# 4_cyber60-alps_periferals.net
KiCad netlist of a schematic drawn in Altium Designer
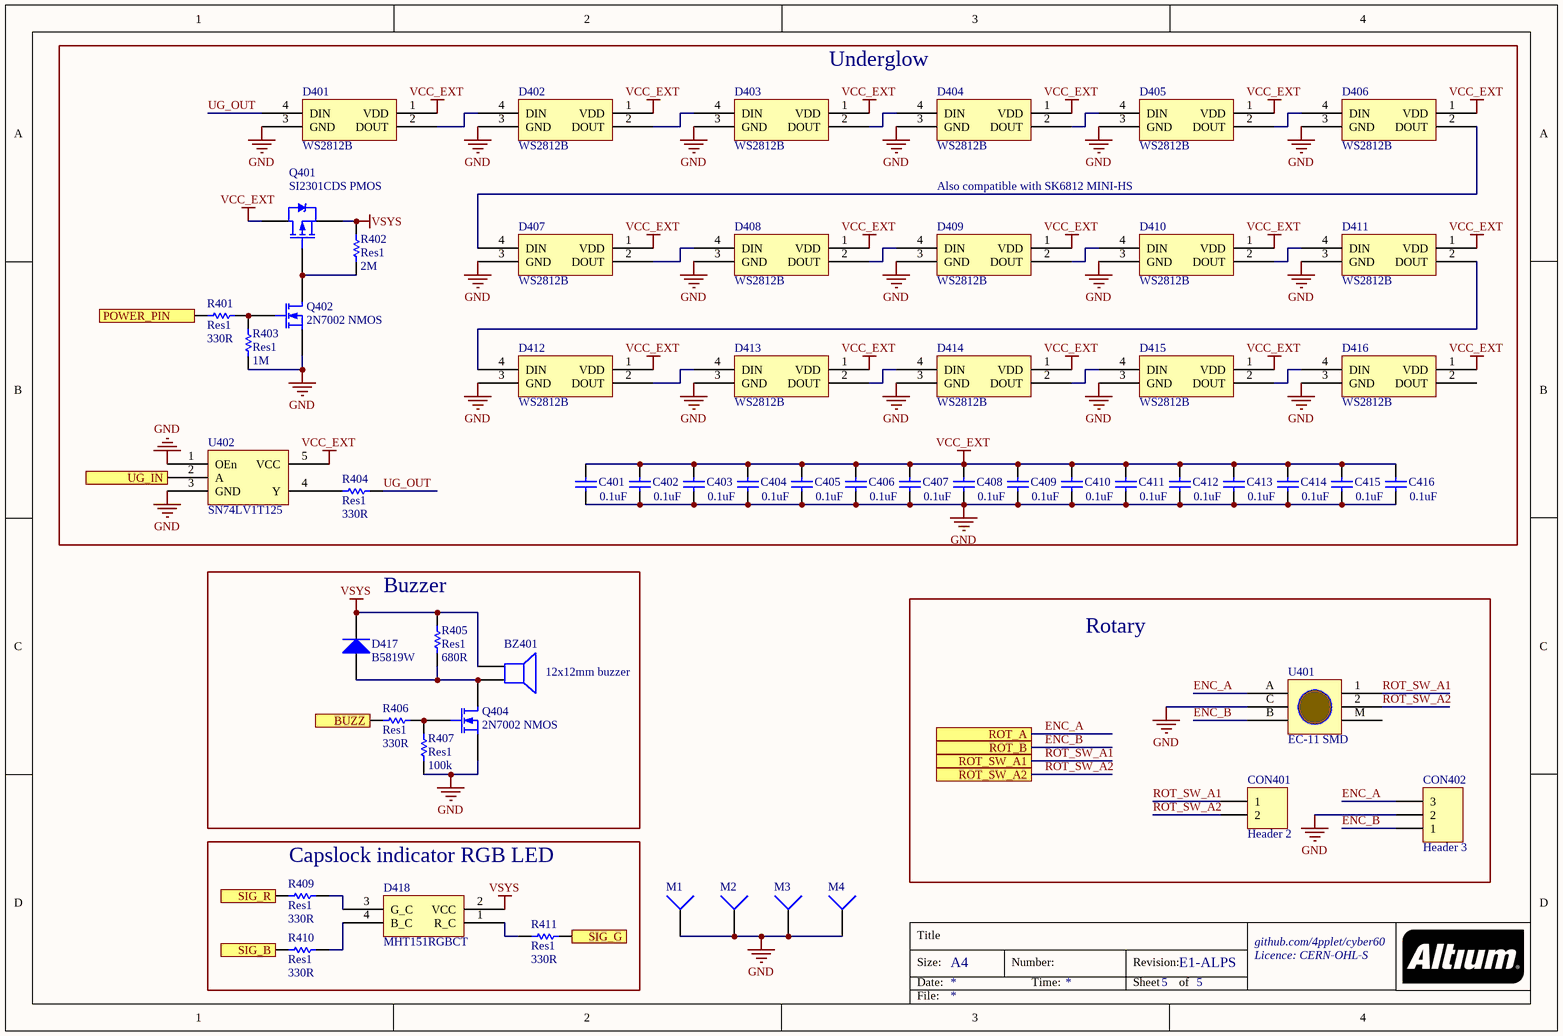
[diagram p0: 4_cyber60-alps_periferals.SchDoc]

(export (version "E")
  (design (tool "Eeschema 10.0.6"))
  (components
    (comp (ref "BZ401")
      (value "12x12mm buzzer")
      (footprint "buzzer 12x12")
      (description "Loudspeaker")
      (fields (field (name "LCSC PART #") "C409829") (field (name "MRF.PART") "YS-SBZ1230"))
      (libsource (lib "Miscellaneous Devices") (part "Speaker"))
    )
    (comp (ref "C401")
      (value "0.1uF")
      (footprint "C0603[1608]")
      (description "Capacitor")
      (fields (field (name "MFG") "KEMET") (field (name "LCSC PART #") "C14663"))
      (libsource (lib "Miscellaneous Devices") (part "Cap"))
    )
    (comp (ref "C402")
      (value "0.1uF")
      (footprint "C0603[1608]")
      (description "Capacitor")
      (fields (field (name "MFG") "KEMET") (field (name "LCSC PART #") "C14663"))
      (libsource (lib "Miscellaneous Devices") (part "Cap"))
    )
    (comp (ref "C403")
      (value "0.1uF")
      (footprint "C0603[1608]")
      (description "Capacitor")
      (fields (field (name "MFG") "KEMET") (field (name "LCSC PART #") "C14663"))
      (libsource (lib "Miscellaneous Devices") (part "Cap"))
    )
    (comp (ref "C404")
      (value "0.1uF")
      (footprint "C0603[1608]")
      (description "Capacitor")
      (fields (field (name "MFG") "KEMET") (field (name "LCSC PART #") "C14663"))
      (libsource (lib "Miscellaneous Devices") (part "Cap"))
    )
    (comp (ref "C405")
      (value "0.1uF")
      (footprint "C0603[1608]")
      (description "Capacitor")
      (fields (field (name "MFG") "KEMET") (field (name "LCSC PART #") "C14663"))
      (libsource (lib "Miscellaneous Devices") (part "Cap"))
    )
    (comp (ref "C406")
      (value "0.1uF")
      (footprint "C0603[1608]")
      (description "Capacitor")
      (fields (field (name "MFG") "KEMET") (field (name "LCSC PART #") "C14663"))
      (libsource (lib "Miscellaneous Devices") (part "Cap"))
    )
    (comp (ref "C407")
      (value "0.1uF")
      (footprint "C0603[1608]")
      (description "Capacitor")
      (fields (field (name "MFG") "KEMET") (field (name "LCSC PART #") "C14663"))
      (libsource (lib "Miscellaneous Devices") (part "Cap"))
    )
    (comp (ref "C408")
      (value "0.1uF")
      (footprint "C0603[1608]")
      (description "Capacitor")
      (fields (field (name "MFG") "KEMET") (field (name "LCSC PART #") "C14663"))
      (libsource (lib "Miscellaneous Devices") (part "Cap"))
    )
    (comp (ref "C409")
      (value "0.1uF")
      (footprint "C0603[1608]")
      (description "Capacitor")
      (fields (field (name "MFG") "KEMET") (field (name "LCSC PART #") "C14663"))
      (libsource (lib "Miscellaneous Devices") (part "Cap"))
    )
    (comp (ref "C410")
      (value "0.1uF")
      (footprint "C0603[1608]")
      (description "Capacitor")
      (fields (field (name "MFG") "KEMET") (field (name "LCSC PART #") "C14663"))
      (libsource (lib "Miscellaneous Devices") (part "Cap"))
    )
    (comp (ref "C411")
      (value "0.1uF")
      (footprint "C0603[1608]")
      (description "Capacitor")
      (fields (field (name "MFG") "KEMET") (field (name "LCSC PART #") "C14663"))
      (libsource (lib "Miscellaneous Devices") (part "Cap"))
    )
    (comp (ref "C412")
      (value "0.1uF")
      (footprint "C0603[1608]")
      (description "Capacitor")
      (fields (field (name "MFG") "KEMET") (field (name "LCSC PART #") "C14663"))
      (libsource (lib "Miscellaneous Devices") (part "Cap"))
    )
    (comp (ref "C413")
      (value "0.1uF")
      (footprint "C0603[1608]")
      (description "Capacitor")
      (fields (field (name "MFG") "KEMET") (field (name "LCSC PART #") "C14663"))
      (libsource (lib "Miscellaneous Devices") (part "Cap"))
    )
    (comp (ref "C414")
      (value "0.1uF")
      (footprint "C0603[1608]")
      (description "Capacitor")
      (fields (field (name "MFG") "KEMET") (field (name "LCSC PART #") "C14663"))
      (libsource (lib "Miscellaneous Devices") (part "Cap"))
    )
    (comp (ref "C415")
      (value "0.1uF")
      (footprint "C0603[1608]")
      (description "Capacitor")
      (fields (field (name "MFG") "KEMET") (field (name "LCSC PART #") "C14663"))
      (libsource (lib "Miscellaneous Devices") (part "Cap"))
    )
    (comp (ref "C416")
      (value "0.1uF")
      (footprint "C0603[1608]")
      (description "Capacitor")
      (fields (field (name "MFG") "KEMET") (field (name "LCSC PART #") "C14663"))
      (libsource (lib "Miscellaneous Devices") (part "Cap"))
    )
    (comp (ref "CON401")
      (value "Header 2")
      (footprint "HDR1X2")
      (description "Header, 2-Pin")
      (libsource (lib "Miscellaneous Connectors") (part "Header 2"))
    )
    (comp (ref "CON402")
      (value "Header 3")
      (footprint "HDR1X3")
      (description "Header, 3-Pin")
      (libsource (lib "Miscellaneous Connectors") (part "Header 3"))
    )
    (comp (ref "D401")
      (value "WS2812B")
      (footprint "WS2812B - 2020")
      (fields (field (name "LCSC PART #") "C965556") (field (name "MRF.PART") "WS2812C-2020"))
      (libsource (lib "Keebs") (part "WS2812B"))
    )
    (comp (ref "D402")
      (value "WS2812B")
      (footprint "WS2812B - 2020")
      (fields (field (name "LCSC PART #") "C965556") (field (name "MRF.PART") "WS2812C-2020"))
      (libsource (lib "Keebs") (part "WS2812B"))
    )
    (comp (ref "D403")
      (value "WS2812B")
      (footprint "WS2812B - 2020")
      (fields (field (name "LCSC PART #") "C965556") (field (name "MRF.PART") "WS2812C-2020"))
      (libsource (lib "Keebs") (part "WS2812B"))
    )
    (comp (ref "D404")
      (value "WS2812B")
      (footprint "WS2812B - 2020")
      (fields (field (name "LCSC PART #") "C965556") (field (name "MRF.PART") "WS2812C-2020"))
      (libsource (lib "Keebs") (part "WS2812B"))
    )
    (comp (ref "D405")
      (value "WS2812B")
      (footprint "WS2812B - 2020")
      (fields (field (name "LCSC PART #") "C965556") (field (name "MRF.PART") "WS2812C-2020"))
      (libsource (lib "Keebs") (part "WS2812B"))
    )
    (comp (ref "D406")
      (value "WS2812B")
      (footprint "WS2812B - 2020")
      (fields (field (name "LCSC PART #") "C965556") (field (name "MRF.PART") "WS2812C-2020"))
      (libsource (lib "Keebs") (part "WS2812B"))
    )
    (comp (ref "D407")
      (value "WS2812B")
      (footprint "WS2812B - 2020")
      (fields (field (name "LCSC PART #") "C965556") (field (name "MRF.PART") "WS2812C-2020"))
      (libsource (lib "Keebs") (part "WS2812B"))
    )
    (comp (ref "D408")
      (value "WS2812B")
      (footprint "WS2812B - 2020")
      (fields (field (name "LCSC PART #") "C965556") (field (name "MRF.PART") "WS2812C-2020"))
      (libsource (lib "Keebs") (part "WS2812B"))
    )
    (comp (ref "D409")
      (value "WS2812B")
      (footprint "WS2812B - 2020")
      (fields (field (name "LCSC PART #") "C965556") (field (name "MRF.PART") "WS2812C-2020"))
      (libsource (lib "Keebs") (part "WS2812B"))
    )
    (comp (ref "D410")
      (value "WS2812B")
      (footprint "WS2812B - 2020")
      (fields (field (name "LCSC PART #") "C965556") (field (name "MRF.PART") "WS2812C-2020"))
      (libsource (lib "Keebs") (part "WS2812B"))
    )
    (comp (ref "D411")
      (value "WS2812B")
      (footprint "WS2812B - 2020")
      (fields (field (name "LCSC PART #") "C965556") (field (name "MRF.PART") "WS2812C-2020"))
      (libsource (lib "Keebs") (part "WS2812B"))
    )
    (comp (ref "D412")
      (value "WS2812B")
      (footprint "WS2812B - 2020")
      (fields (field (name "LCSC PART #") "C965556") (field (name "MRF.PART") "WS2812C-2020"))
      (libsource (lib "Keebs") (part "WS2812B"))
    )
    (comp (ref "D413")
      (value "WS2812B")
      (footprint "WS2812B - 2020")
      (fields (field (name "LCSC PART #") "C965556") (field (name "MRF.PART") "WS2812C-2020"))
      (libsource (lib "Keebs") (part "WS2812B"))
    )
    (comp (ref "D414")
      (value "WS2812B")
      (footprint "WS2812B - 2020")
      (fields (field (name "LCSC PART #") "C965556") (field (name "MRF.PART") "WS2812C-2020"))
      (libsource (lib "Keebs") (part "WS2812B"))
    )
    (comp (ref "D415")
      (value "WS2812B")
      (footprint "WS2812B - 2020")
      (fields (field (name "LCSC PART #") "C965556") (field (name "MRF.PART") "WS2812C-2020"))
      (libsource (lib "Keebs") (part "WS2812B"))
    )
    (comp (ref "D416")
      (value "WS2812B")
      (footprint "WS2812B - 2020")
      (fields (field (name "LCSC PART #") "C965556") (field (name "MRF.PART") "WS2812C-2020"))
      (libsource (lib "Keebs") (part "WS2812B"))
    )
    (comp (ref "D417")
      (value "B5819W")
      (footprint "SOD-123")
      (description "Default Diode")
      (fields (field (name "LCSC PART #") "C8598"))
      (libsource (lib "Miscellaneous Devices") (part "Diode"))
    )
    (comp (ref "D418")
      (value "MHT151RGBCT")
      (footprint "MHT151RGBCT")
      (fields (field (name "LCSC PART #") "C2802677") (field (name "MRF.PART") "E6CC1205RGBC3UDA"))
      (libsource (lib "Keebs") (part "MHT151RGBCT"))
    )
    (comp (ref "M1")
      (value "Socket")
      (footprint "mounting_hole")
      (fields (field (name "PUBLISHER") "Altium Limited"))
      (libsource (lib "Miscellaneous Connectors") (part "Socket"))
    )
    (comp (ref "M2")
      (value "Socket")
      (footprint "mounting_hole")
      (fields (field (name "PUBLISHER") "Altium Limited"))
      (libsource (lib "Miscellaneous Connectors") (part "Socket"))
    )
    (comp (ref "M3")
      (value "Socket")
      (footprint "mounting_hole")
      (fields (field (name "PUBLISHER") "Altium Limited"))
      (libsource (lib "Miscellaneous Connectors") (part "Socket"))
    )
    (comp (ref "M4")
      (value "Socket")
      (footprint "mounting_hole")
      (fields (field (name "PUBLISHER") "Altium Limited"))
      (libsource (lib "Miscellaneous Connectors") (part "Socket"))
    )
    (comp (ref "Q401")
      (value "SI2301CDS PMOS")
      (footprint "SOT-23-3")
      (description "P-Channel Power MOSFET")
      (fields (field (name "MRF.PART") "SI2301CDS-T1-GE3") (field (name "LCSC PART #") "C10487"))
      (libsource (lib "Miscellaneous Devices") (part "PMOS-2"))
    )
    (comp (ref "Q402")
      (value "2N7002 NMOS")
      (footprint "SOT-23-3")
      (description "N-Channel MOSFET")
      (fields (field (name "LCSC PART #") "C8545") (field (name "MRF.PART") "2N7002"))
      (libsource (lib "Miscellaneous Devices") (part "MOSFET-N"))
    )
    (comp (ref "Q404")
      (value "2N7002 NMOS")
      (footprint "SOT-23-3")
      (description "N-Channel MOSFET")
      (fields (field (name "LCSC PART #") "C8545") (field (name "MRF.PART") "2N7002"))
      (libsource (lib "Miscellaneous Devices") (part "MOSFET-N"))
    )
    (comp (ref "R401")
      (value "Res1")
      (footprint "R0603[1608]")
      (description "Resistor")
      (fields
        (field (name "ALTIUM_VALUE") "330R")
        (field (name "LCSC PART #") "C23138")
        (field (name "MRF.PART") "0603WAF3300T5E")
      )
      (libsource (lib "Miscellaneous Devices") (part "Res1"))
    )
    (comp (ref "R402")
      (value "Res1")
      (footprint "R0603[1608]")
      (description "Resistor")
      (fields
        (field (name "ALTIUM_VALUE") "2M")
        (field (name "MRF.PART") "0603WAF2004T5E")
        (field (name "LCSC PART #") "C22976")
      )
      (libsource (lib "Miscellaneous Devices") (part "Res1"))
    )
    (comp (ref "R403")
      (value "Res1")
      (footprint "R0603[1608]")
      (description "Resistor")
      (fields
        (field (name "ALTIUM_VALUE") "1M")
        (field (name "MRF.PART") "0603WAF1004T5E")
        (field (name "LCSC PART #") "C22935")
      )
      (libsource (lib "Miscellaneous Devices") (part "Res1"))
    )
    (comp (ref "R404")
      (value "Res1")
      (footprint "R0603[1608]")
      (description "Resistor")
      (fields
        (field (name "ALTIUM_VALUE") "330R")
        (field (name "LCSC PART #") "C23138")
        (field (name "MRF.PART") "0603WAF3300T5E")
      )
      (libsource (lib "Miscellaneous Devices") (part "Res1"))
    )
    (comp (ref "R405")
      (value "Res1")
      (footprint "R0603[1608]")
      (description "Resistor")
      (fields
        (field (name "ALTIUM_VALUE") "680R")
        (field (name "MRF.PART") "0603WAF6800T5E")
        (field (name "LCSC PART #") "C23228")
      )
      (libsource (lib "Miscellaneous Devices") (part "Res1"))
    )
    (comp (ref "R406")
      (value "Res1")
      (footprint "R0603[1608]")
      (description "Resistor")
      (fields
        (field (name "ALTIUM_VALUE") "330R")
        (field (name "LCSC PART #") "C23138")
        (field (name "MRF.PART") "0603WAF3300T5E")
      )
      (libsource (lib "Miscellaneous Devices") (part "Res1"))
    )
    (comp (ref "R407")
      (value "Res1")
      (footprint "R0603[1608]")
      (description "Resistor")
      (fields
        (field (name "ALTIUM_VALUE") "100k")
        (field (name "MRF.PART") "0603WAF1003T5E")
        (field (name "LCSC PART #") "C25803")
      )
      (libsource (lib "Miscellaneous Devices") (part "Res1"))
    )
    (comp (ref "R409")
      (value "Res1")
      (footprint "R0603[1608]")
      (description "Resistor")
      (fields
        (field (name "ALTIUM_VALUE") "330R")
        (field (name "LCSC PART #") "C23138")
        (field (name "MRF.PART") "0603WAF3300T5E")
      )
      (libsource (lib "Miscellaneous Devices") (part "Res1"))
    )
    (comp (ref "R410")
      (value "Res1")
      (footprint "R0603[1608]")
      (description "Resistor")
      (fields
        (field (name "ALTIUM_VALUE") "330R")
        (field (name "LCSC PART #") "C23138")
        (field (name "MRF.PART") "0603WAF3300T5E")
      )
      (libsource (lib "Miscellaneous Devices") (part "Res1"))
    )
    (comp (ref "R411")
      (value "Res1")
      (footprint "R0603[1608]")
      (description "Resistor")
      (fields
        (field (name "ALTIUM_VALUE") "330R")
        (field (name "LCSC PART #") "C23138")
        (field (name "MRF.PART") "0603WAF3300T5E")
      )
      (libsource (lib "Miscellaneous Devices") (part "Res1"))
    )
    (comp (ref "U401") (value "EC-11 SMD") (footprint "EC11-SMD") (libsource (lib "Keebs") (part "EC-11")))
    (comp (ref "U402")
      (value "SN74LV1T125")
      (footprint "SOT-23-5")
      (description "SN74LV1T125 or SN74LV1T34. Connect OE to GND")
      (fields (field (name "LCSC PART #") "C473338") (field (name "MRF.PART") "SN74LV1T125DBVR"))
      (libsource (lib "Keebs") (part "SN74LV1T125"))
    )
  )
  (nets
    (net (code "1") (name "/BUZZ") (class "Default")
      (node (ref "R406") (pin "2") (pinfunction "2_2") (pintype "passive"))
    )
    (net (code "2") (name "/ENC_A") (class "Default")
      (node (ref "CON402") (pin "3") (pinfunction "3_3") (pintype "passive"))
      (node (ref "U401") (pin "A") (pinfunction "B_A") (pintype "passive"))
    )
    (net (code "3") (name "/ENC_B") (class "Default")
      (node (ref "CON402") (pin "1") (pinfunction "1_1") (pintype "passive"))
      (node (ref "U401") (pin "B") (pinfunction "B_B") (pintype "passive"))
    )
    (net (code "4") (name "/POWER_PIN") (class "Default")
      (node (ref "R401") (pin "1") (pinfunction "1_1") (pintype "passive"))
    )
    (net (code "5") (name "/ROT_SW_A1") (class "Default")
      (node (ref "CON401") (pin "1") (pinfunction "1_1") (pintype "passive"))
      (node (ref "U401") (pin "1") (pinfunction "1_1") (pintype "passive"))
    )
    (net (code "6") (name "/ROT_SW_A2") (class "Default")
      (node (ref "CON401") (pin "2") (pinfunction "2_2") (pintype "passive"))
      (node (ref "U401") (pin "2") (pinfunction "2_2") (pintype "passive"))
    )
    (net (code "7") (name "/SIG_B") (class "Default")
      (node (ref "R410") (pin "2") (pinfunction "2_2") (pintype "passive"))
    )
    (net (code "8") (name "/SIG_G") (class "Default")
      (node (ref "R411") (pin "1") (pinfunction "1_1") (pintype "passive"))
    )
    (net (code "9") (name "/SIG_R") (class "Default")
      (node (ref "R409") (pin "2") (pinfunction "2_2") (pintype "passive"))
    )
    (net (code "10") (name "/UG_IN") (class "Default")
      (node (ref "U402") (pin "2") (pinfunction "A_2") (pintype "passive"))
    )
    (net (code "11") (name "/UG_OUT") (class "Default")
      (node (ref "D401") (pin "4") (pinfunction "DIN_4") (pintype "passive"))
      (node (ref "R404") (pin "1") (pinfunction "1_1") (pintype "passive"))
    )
    (net (code "12") (name "GND") (class "Default")
      (node (ref "C401") (pin "1") (pinfunction "1_1") (pintype "passive"))
      (node (ref "C402") (pin "1") (pinfunction "1_1") (pintype "passive"))
      (node (ref "C403") (pin "1") (pinfunction "1_1") (pintype "passive"))
      (node (ref "C404") (pin "1") (pinfunction "1_1") (pintype "passive"))
      (node (ref "C405") (pin "1") (pinfunction "1_1") (pintype "passive"))
      (node (ref "C406") (pin "1") (pinfunction "1_1") (pintype "passive"))
      (node (ref "C407") (pin "1") (pinfunction "1_1") (pintype "passive"))
      (node (ref "C408") (pin "1") (pinfunction "1_1") (pintype "passive"))
      (node (ref "C409") (pin "1") (pinfunction "1_1") (pintype "passive"))
      (node (ref "C410") (pin "1") (pinfunction "1_1") (pintype "passive"))
      (node (ref "C411") (pin "1") (pinfunction "1_1") (pintype "passive"))
      (node (ref "C412") (pin "1") (pinfunction "1_1") (pintype "passive"))
      (node (ref "C413") (pin "1") (pinfunction "1_1") (pintype "passive"))
      (node (ref "C414") (pin "1") (pinfunction "1_1") (pintype "passive"))
      (node (ref "C415") (pin "1") (pinfunction "1_1") (pintype "passive"))
      (node (ref "C416") (pin "1") (pinfunction "1_1") (pintype "passive"))
      (node (ref "CON402") (pin "2") (pinfunction "2_2") (pintype "passive"))
      (node (ref "D401") (pin "3") (pinfunction "GND_3") (pintype "passive"))
      (node (ref "D402") (pin "3") (pinfunction "GND_3") (pintype "passive"))
      (node (ref "D403") (pin "3") (pinfunction "GND_3") (pintype "passive"))
      (node (ref "D404") (pin "3") (pinfunction "GND_3") (pintype "passive"))
      (node (ref "D405") (pin "3") (pinfunction "GND_3") (pintype "passive"))
      (node (ref "D406") (pin "3") (pinfunction "GND_3") (pintype "passive"))
      (node (ref "D407") (pin "3") (pinfunction "GND_3") (pintype "passive"))
      (node (ref "D408") (pin "3") (pinfunction "GND_3") (pintype "passive"))
      (node (ref "D409") (pin "3") (pinfunction "GND_3") (pintype "passive"))
      (node (ref "D410") (pin "3") (pinfunction "GND_3") (pintype "passive"))
      (node (ref "D411") (pin "3") (pinfunction "GND_3") (pintype "passive"))
      (node (ref "D412") (pin "3") (pinfunction "GND_3") (pintype "passive"))
      (node (ref "D413") (pin "3") (pinfunction "GND_3") (pintype "passive"))
      (node (ref "D414") (pin "3") (pinfunction "GND_3") (pintype "passive"))
      (node (ref "D415") (pin "3") (pinfunction "GND_3") (pintype "passive"))
      (node (ref "D416") (pin "3") (pinfunction "GND_3") (pintype "passive"))
      (node (ref "M1") (pin "1") (pinfunction "1_1") (pintype "passive"))
      (node (ref "M2") (pin "1") (pinfunction "1_1") (pintype "passive"))
      (node (ref "M3") (pin "1") (pinfunction "1_1") (pintype "passive"))
      (node (ref "M4") (pin "1") (pinfunction "1_1") (pintype "passive"))
      (node (ref "Q402") (pin "2") (pinfunction "S_2") (pintype "passive"))
      (node (ref "Q404") (pin "2") (pinfunction "S_2") (pintype "passive"))
      (node (ref "R403") (pin "2") (pinfunction "2_2") (pintype "passive"))
      (node (ref "R407") (pin "2") (pinfunction "2_2") (pintype "passive"))
      (node (ref "U401") (pin "C") (pinfunction "C_C") (pintype "passive"))
      (node (ref "U402") (pin "1") (pinfunction "OEn_1") (pintype "passive"))
      (node (ref "U402") (pin "3") (pinfunction "GND_3") (pintype "passive"))
    )
    (net (code "13") (name "Net-(D401-DOUT)") (class "Default")
      (node (ref "D401") (pin "2") (pinfunction "DOUT_2") (pintype "passive"))
      (node (ref "D402") (pin "4") (pinfunction "DIN_4") (pintype "passive"))
    )
    (net (code "14") (name "Net-(D402-DOUT)") (class "Default")
      (node (ref "D402") (pin "2") (pinfunction "DOUT_2") (pintype "passive"))
      (node (ref "D403") (pin "4") (pinfunction "DIN_4") (pintype "passive"))
    )
    (net (code "15") (name "Net-(D403-DOUT)") (class "Default")
      (node (ref "D403") (pin "2") (pinfunction "DOUT_2") (pintype "passive"))
      (node (ref "D404") (pin "4") (pinfunction "DIN_4") (pintype "passive"))
    )
    (net (code "16") (name "Net-(D404-DOUT)") (class "Default")
      (node (ref "D404") (pin "2") (pinfunction "DOUT_2") (pintype "passive"))
      (node (ref "D405") (pin "4") (pinfunction "DIN_4") (pintype "passive"))
    )
    (net (code "17") (name "Net-(D405-DOUT)") (class "Default")
      (node (ref "D405") (pin "2") (pinfunction "DOUT_2") (pintype "passive"))
      (node (ref "D406") (pin "4") (pinfunction "DIN_4") (pintype "passive"))
    )
    (net (code "18") (name "Net-(D406-DOUT)") (class "Default")
      (node (ref "D406") (pin "2") (pinfunction "DOUT_2") (pintype "passive"))
      (node (ref "D407") (pin "4") (pinfunction "DIN_4") (pintype "passive"))
    )
    (net (code "19") (name "Net-(D407-DOUT)") (class "Default")
      (node (ref "D407") (pin "2") (pinfunction "DOUT_2") (pintype "passive"))
      (node (ref "D408") (pin "4") (pinfunction "DIN_4") (pintype "passive"))
    )
    (net (code "20") (name "Net-(D408-DOUT)") (class "Default")
      (node (ref "D408") (pin "2") (pinfunction "DOUT_2") (pintype "passive"))
      (node (ref "D409") (pin "4") (pinfunction "DIN_4") (pintype "passive"))
    )
    (net (code "21") (name "Net-(D409-DOUT)") (class "Default")
      (node (ref "D409") (pin "2") (pinfunction "DOUT_2") (pintype "passive"))
      (node (ref "D410") (pin "4") (pinfunction "DIN_4") (pintype "passive"))
    )
    (net (code "22") (name "Net-(D410-DOUT)") (class "Default")
      (node (ref "D410") (pin "2") (pinfunction "DOUT_2") (pintype "passive"))
      (node (ref "D411") (pin "4") (pinfunction "DIN_4") (pintype "passive"))
    )
    (net (code "23") (name "Net-(D411-DOUT)") (class "Default")
      (node (ref "D411") (pin "2") (pinfunction "DOUT_2") (pintype "passive"))
      (node (ref "D412") (pin "4") (pinfunction "DIN_4") (pintype "passive"))
    )
    (net (code "24") (name "Net-(D412-DOUT)") (class "Default")
      (node (ref "D412") (pin "2") (pinfunction "DOUT_2") (pintype "passive"))
      (node (ref "D413") (pin "4") (pinfunction "DIN_4") (pintype "passive"))
    )
    (net (code "25") (name "Net-(D413-DOUT)") (class "Default")
      (node (ref "D413") (pin "2") (pinfunction "DOUT_2") (pintype "passive"))
      (node (ref "D414") (pin "4") (pinfunction "DIN_4") (pintype "passive"))
    )
    (net (code "26") (name "Net-(D414-DOUT)") (class "Default")
      (node (ref "D414") (pin "2") (pinfunction "DOUT_2") (pintype "passive"))
      (node (ref "D415") (pin "4") (pinfunction "DIN_4") (pintype "passive"))
    )
    (net (code "27") (name "Net-(D415-DOUT)") (class "Default")
      (node (ref "D415") (pin "2") (pinfunction "DOUT_2") (pintype "passive"))
      (node (ref "D416") (pin "4") (pinfunction "DIN_4") (pintype "passive"))
    )
    (net (code "28") (name "Net-(D417-A)") (class "Default")
      (node (ref "BZ401") (pin "2") (pinfunction "2_2") (pintype "passive"))
      (node (ref "D417") (pin "1") (pinfunction "A_1") (pintype "passive"))
      (node (ref "Q404") (pin "3") (pinfunction "D_3") (pintype "passive"))
      (node (ref "R405") (pin "2") (pinfunction "2_2") (pintype "passive"))
    )
    (net (code "29") (name "Net-(D418-B_C)") (class "Default")
      (node (ref "D418") (pin "4") (pinfunction "B_C_4") (pintype "passive"))
      (node (ref "R410") (pin "1") (pinfunction "1_1") (pintype "passive"))
    )
    (net (code "30") (name "Net-(D418-G_C)") (class "Default")
      (node (ref "D418") (pin "3") (pinfunction "G_C_3") (pintype "passive"))
      (node (ref "R409") (pin "1") (pinfunction "1_1") (pintype "passive"))
    )
    (net (code "31") (name "Net-(D418-R_C)") (class "Default")
      (node (ref "D418") (pin "1") (pinfunction "R_C_1") (pintype "passive"))
      (node (ref "R411") (pin "2") (pinfunction "2_2") (pintype "passive"))
    )
    (net (code "32") (name "Net-(Q401-G)") (class "Default")
      (node (ref "Q401") (pin "1") (pinfunction "G_1") (pintype "passive"))
      (node (ref "Q402") (pin "3") (pinfunction "D_3") (pintype "passive"))
      (node (ref "R402") (pin "1") (pinfunction "1_1") (pintype "passive"))
    )
    (net (code "33") (name "Net-(Q402-G)") (class "Default")
      (node (ref "Q402") (pin "1") (pinfunction "G_1") (pintype "passive"))
      (node (ref "R401") (pin "2") (pinfunction "2_2") (pintype "passive"))
      (node (ref "R403") (pin "1") (pinfunction "1_1") (pintype "passive"))
    )
    (net (code "34") (name "Net-(Q404-G)") (class "Default")
      (node (ref "Q404") (pin "1") (pinfunction "G_1") (pintype "passive"))
      (node (ref "R406") (pin "1") (pinfunction "1_1") (pintype "passive"))
      (node (ref "R407") (pin "1") (pinfunction "1_1") (pintype "passive"))
    )
    (net (code "35") (name "Net-(U402-Y)") (class "Default")
      (node (ref "R404") (pin "2") (pinfunction "2_2") (pintype "passive"))
      (node (ref "U402") (pin "4") (pinfunction "Y_4") (pintype "passive"))
    )
    (net (code "36") (name "VCC_EXT") (class "Default")
      (node (ref "C401") (pin "2") (pinfunction "2_2") (pintype "passive"))
      (node (ref "C402") (pin "2") (pinfunction "2_2") (pintype "passive"))
      (node (ref "C403") (pin "2") (pinfunction "2_2") (pintype "passive"))
      (node (ref "C404") (pin "2") (pinfunction "2_2") (pintype "passive"))
      (node (ref "C405") (pin "2") (pinfunction "2_2") (pintype "passive"))
      (node (ref "C406") (pin "2") (pinfunction "2_2") (pintype "passive"))
      (node (ref "C407") (pin "2") (pinfunction "2_2") (pintype "passive"))
      (node (ref "C408") (pin "2") (pinfunction "2_2") (pintype "passive"))
      (node (ref "C409") (pin "2") (pinfunction "2_2") (pintype "passive"))
      (node (ref "C410") (pin "2") (pinfunction "2_2") (pintype "passive"))
      (node (ref "C411") (pin "2") (pinfunction "2_2") (pintype "passive"))
      (node (ref "C412") (pin "2") (pinfunction "2_2") (pintype "passive"))
      (node (ref "C413") (pin "2") (pinfunction "2_2") (pintype "passive"))
      (node (ref "C414") (pin "2") (pinfunction "2_2") (pintype "passive"))
      (node (ref "C415") (pin "2") (pinfunction "2_2") (pintype "passive"))
      (node (ref "C416") (pin "2") (pinfunction "2_2") (pintype "passive"))
      (node (ref "D401") (pin "1") (pinfunction "VDD_1") (pintype "passive"))
      (node (ref "D402") (pin "1") (pinfunction "VDD_1") (pintype "passive"))
      (node (ref "D403") (pin "1") (pinfunction "VDD_1") (pintype "passive"))
      (node (ref "D404") (pin "1") (pinfunction "VDD_1") (pintype "passive"))
      (node (ref "D405") (pin "1") (pinfunction "VDD_1") (pintype "passive"))
      (node (ref "D406") (pin "1") (pinfunction "VDD_1") (pintype "passive"))
      (node (ref "D407") (pin "1") (pinfunction "VDD_1") (pintype "passive"))
      (node (ref "D408") (pin "1") (pinfunction "VDD_1") (pintype "passive"))
      (node (ref "D409") (pin "1") (pinfunction "VDD_1") (pintype "passive"))
      (node (ref "D410") (pin "1") (pinfunction "VDD_1") (pintype "passive"))
      (node (ref "D411") (pin "1") (pinfunction "VDD_1") (pintype "passive"))
      (node (ref "D412") (pin "1") (pinfunction "VDD_1") (pintype "passive"))
      (node (ref "D413") (pin "1") (pinfunction "VDD_1") (pintype "passive"))
      (node (ref "D414") (pin "1") (pinfunction "VDD_1") (pintype "passive"))
      (node (ref "D415") (pin "1") (pinfunction "VDD_1") (pintype "passive"))
      (node (ref "D416") (pin "1") (pinfunction "VDD_1") (pintype "passive"))
      (node (ref "Q401") (pin "3") (pinfunction "D_3") (pintype "passive"))
      (node (ref "U402") (pin "5") (pinfunction "VCC_5") (pintype "passive"))
    )
    (net (code "37") (name "VSYS") (class "Default")
      (node (ref "BZ401") (pin "1") (pinfunction "1_1") (pintype "passive"))
      (node (ref "D417") (pin "2") (pinfunction "K_2") (pintype "passive"))
      (node (ref "D418") (pin "2") (pinfunction "VCC_2") (pintype "passive"))
      (node (ref "Q401") (pin "2") (pinfunction "S_2") (pintype "passive"))
      (node (ref "R402") (pin "2") (pinfunction "2_2") (pintype "passive"))
      (node (ref "R405") (pin "1") (pinfunction "1_1") (pintype "passive"))
    )
    (net (code "38") (name "unconnected-(D416-DOUT-Pad2)") (class "Default")
      (node (ref "D416") (pin "2") (pinfunction "DOUT_2") (pintype "passive"))
    )
    (net (code "39") (name "unconnected-(U401-PadM)") (class "Default")
      (node (ref "U401") (pin "M") (pinfunction "M_M") (pintype "passive"))
    )
  )
)
